# RT1064_Interaction.net
KiCad netlist of a schematic drawn in Altium Designer
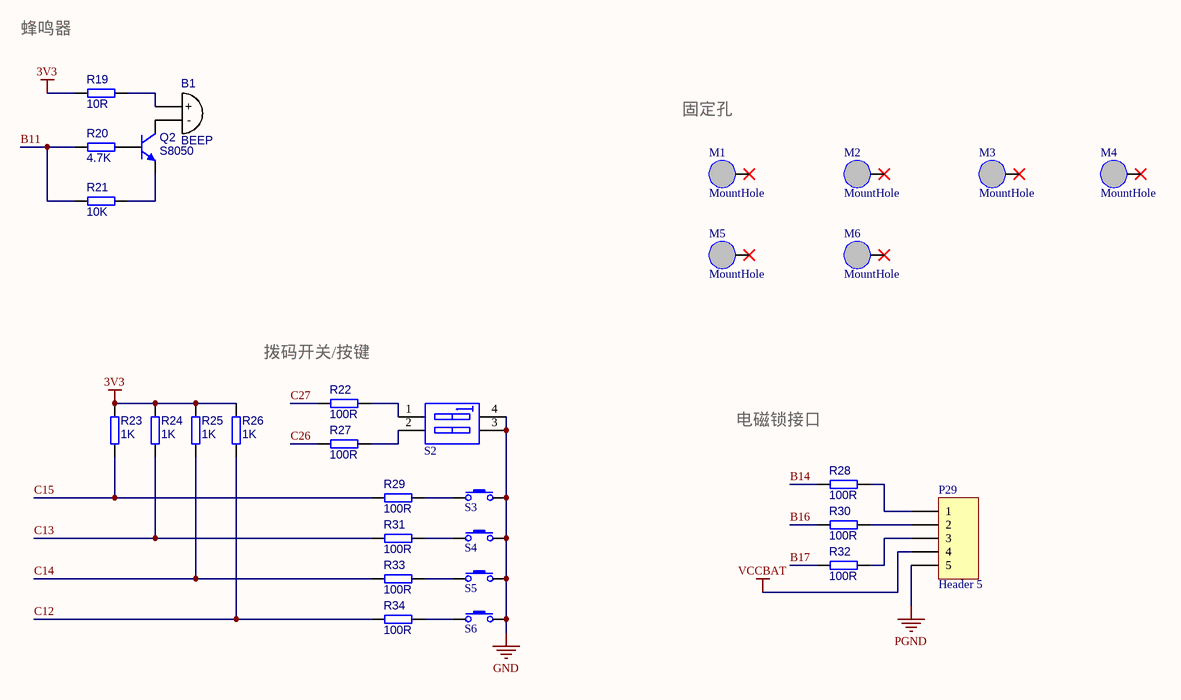
[diagram p0: RT1064_Interaction.SchDoc]

(export (version "E")
  (design (tool "Eeschema 10.0.6"))
  (components
    (comp (ref "B1")
      (value "BEEP")
      (footprint "BEEP 9x5.5mm")
      (description "蜂鸣器")
      (libsource (lib "RT1064_V1主板器件封装集成库") (part "BEEP"))
    )
    (comp (ref "M1")
      (value "MountHole")
      (footprint "M3x12+6_N")
      (description "固定孔")
      (libsource (lib "RT1064_V1主板器件封装集成库") (part "MountHole"))
    )
    (comp (ref "M2")
      (value "MountHole")
      (footprint "M3x12+6_N")
      (description "固定孔")
      (libsource (lib "RT1064_V1主板器件封装集成库") (part "MountHole"))
    )
    (comp (ref "M3")
      (value "MountHole")
      (footprint "M3x12+6_N")
      (description "固定孔")
      (libsource (lib "RT1064_V1主板器件封装集成库") (part "MountHole"))
    )
    (comp (ref "M4")
      (value "MountHole")
      (footprint "M3x12+6_N")
      (description "固定孔")
      (libsource (lib "RT1064_V1主板器件封装集成库") (part "MountHole"))
    )
    (comp (ref "M5")
      (value "MountHole")
      (footprint "M3-MountHole")
      (description "固定孔")
      (libsource (lib "RT1064_V1主板器件封装集成库") (part "MountHole"))
    )
    (comp (ref "M6")
      (value "MountHole")
      (footprint "M3-MountHole")
      (description "固定孔")
      (libsource (lib "RT1064_V1主板器件封装集成库") (part "MountHole"))
    )
    (comp (ref "P29")
      (value "Header 5")
      (footprint "HDR1X5")
      (description "Header, 5-Pin")
      (fields (field (name "PUBLISHER") "Altium Limited"))
      (libsource (lib "Miscellaneous Connectors") (part "Header 5"))
    )
    (comp (ref "Q2")
      (value "S8050")
      (footprint "SOT-23")
      (description "Discrete NPN Bipolar Transistor")
      (fields (field (name "PARTNUMBER") "S8050") (field (name "PUBLISHER") "Altium Limited"))
      (libsource (lib "RT1064_V1主板器件封装集成库") (part "NPN S8050"))
    )
    (comp (ref "R19")
      (value "10R")
      (footprint "RESC1608[0603]S-L")
      (description "贴片电阻")
      (fields (field (name "POWER") "1/8W") (field (name "TOLERANCE") "±1%"))
      (libsource (lib "RT1064_V1主板器件封装集成库") (part "Res-Chip"))
    )
    (comp (ref "R20")
      (value "4.7K")
      (footprint "RESC1608[0603]S-L")
      (description "贴片电阻")
      (fields (field (name "POWER") "1/8W") (field (name "TOLERANCE") "±1%"))
      (libsource (lib "RT1064_V1主板器件封装集成库") (part "Res-Chip"))
    )
    (comp (ref "R21")
      (value "10K")
      (footprint "RESC1608[0603]S-L")
      (description "贴片电阻")
      (fields (field (name "POWER") "1/8W") (field (name "TOLERANCE") "±1%"))
      (libsource (lib "RT1064_V1主板器件封装集成库") (part "Res-Chip"))
    )
    (comp (ref "R22")
      (value "100R")
      (footprint "RESC1608[0603]S-L")
      (description "贴片电阻")
      (fields (field (name "POWER") "1/8W") (field (name "TOLERANCE") "±1%"))
      (libsource (lib "RT1064_V1主板器件封装集成库") (part "Res-Chip"))
    )
    (comp (ref "R23")
      (value "1K")
      (footprint "RESC1608[0603]S-L")
      (description "贴片电阻")
      (fields (field (name "POWER") "1/8W") (field (name "TOLERANCE") "±1%"))
      (libsource (lib "RT1064_V1主板器件封装集成库") (part "Res-Chip"))
    )
    (comp (ref "R24")
      (value "1K")
      (footprint "RESC1608[0603]S-L")
      (description "贴片电阻")
      (fields (field (name "POWER") "1/8W") (field (name "TOLERANCE") "±1%"))
      (libsource (lib "RT1064_V1主板器件封装集成库") (part "Res-Chip"))
    )
    (comp (ref "R25")
      (value "1K")
      (footprint "RESC1608[0603]S-L")
      (description "贴片电阻")
      (fields (field (name "POWER") "1/8W") (field (name "TOLERANCE") "±1%"))
      (libsource (lib "RT1064_V1主板器件封装集成库") (part "Res-Chip"))
    )
    (comp (ref "R26")
      (value "1K")
      (footprint "RESC1608[0603]S-L")
      (description "贴片电阻")
      (fields (field (name "POWER") "1/8W") (field (name "TOLERANCE") "±1%"))
      (libsource (lib "RT1064_V1主板器件封装集成库") (part "Res-Chip"))
    )
    (comp (ref "R27")
      (value "100R")
      (footprint "RESC1608[0603]S-L")
      (description "贴片电阻")
      (fields (field (name "POWER") "1/8W") (field (name "TOLERANCE") "±1%"))
      (libsource (lib "RT1064_V1主板器件封装集成库") (part "Res-Chip"))
    )
    (comp (ref "R28")
      (value "100R")
      (footprint "RESC1608[0603]S-L")
      (description "贴片电阻")
      (fields (field (name "POWER") "1/8W") (field (name "TOLERANCE") "±1%"))
      (libsource (lib "RT1064_V1主板器件封装集成库") (part "Res-Chip"))
    )
    (comp (ref "R29")
      (value "100R")
      (footprint "RESC1608[0603]S-L")
      (description "贴片电阻")
      (fields (field (name "POWER") "1/8W") (field (name "TOLERANCE") "±1%"))
      (libsource (lib "RT1064_V1主板器件封装集成库") (part "Res-Chip"))
    )
    (comp (ref "R30")
      (value "100R")
      (footprint "RESC1608[0603]S-L")
      (description "贴片电阻")
      (fields (field (name "POWER") "1/8W") (field (name "TOLERANCE") "±1%"))
      (libsource (lib "RT1064_V1主板器件封装集成库") (part "Res-Chip"))
    )
    (comp (ref "R31")
      (value "100R")
      (footprint "RESC1608[0603]S-L")
      (description "贴片电阻")
      (fields (field (name "POWER") "1/8W") (field (name "TOLERANCE") "±1%"))
      (libsource (lib "RT1064_V1主板器件封装集成库") (part "Res-Chip"))
    )
    (comp (ref "R32")
      (value "100R")
      (footprint "RESC1608[0603]S-L")
      (description "贴片电阻")
      (fields (field (name "POWER") "1/8W") (field (name "TOLERANCE") "±1%"))
      (libsource (lib "RT1064_V1主板器件封装集成库") (part "Res-Chip"))
    )
    (comp (ref "R33")
      (value "100R")
      (footprint "RESC1608[0603]S-L")
      (description "贴片电阻")
      (fields (field (name "POWER") "1/8W") (field (name "TOLERANCE") "±1%"))
      (libsource (lib "RT1064_V1主板器件封装集成库") (part "Res-Chip"))
    )
    (comp (ref "R34")
      (value "100R")
      (footprint "RESC1608[0603]S-L")
      (description "贴片电阻")
      (fields (field (name "POWER") "1/8W") (field (name "TOLERANCE") "±1%"))
      (libsource (lib "RT1064_V1主板器件封装集成库") (part "Res-Chip"))
    )
    (comp (ref "S2")
      (value "SW DIP-2")
      (footprint "Code SW-2-DIP-2.54")
      (description "2位拨码开关")
      (fields (field (name "PUBLISHER") "Altium Limited"))
      (libsource (lib "RT1064_V1主板器件封装集成库") (part "Code SW-2"))
    )
    (comp (ref "S3")
      (value "Button")
      (footprint "PTS810-3*4-CurvePin")
      (description "按键")
      (fields (field (name "PUBLISHER") "Altium Limited"))
      (libsource (lib "RT1064_V1主板器件封装集成库") (part "KEY"))
    )
    (comp (ref "S4")
      (value "Button")
      (footprint "PTS810-3*4-CurvePin")
      (description "按键")
      (fields (field (name "PUBLISHER") "Altium Limited"))
      (libsource (lib "RT1064_V1主板器件封装集成库") (part "KEY"))
    )
    (comp (ref "S5")
      (value "Button")
      (footprint "PTS810-3*4-CurvePin")
      (description "按键")
      (fields (field (name "PUBLISHER") "Altium Limited"))
      (libsource (lib "RT1064_V1主板器件封装集成库") (part "KEY"))
    )
    (comp (ref "S6")
      (value "Button")
      (footprint "PTS810-3*4-CurvePin")
      (description "按键")
      (fields (field (name "PUBLISHER") "Altium Limited"))
      (libsource (lib "RT1064_V1主板器件封装集成库") (part "KEY"))
    )
  )
  (nets
    (net (code "1") (name "/B11") (class "Default")
      (node (ref "R20") (pin "2") (pinfunction "2_2") (pintype "passive"))
      (node (ref "R21") (pin "2") (pinfunction "2_2") (pintype "passive"))
    )
    (net (code "2") (name "/B14") (class "Default")
      (node (ref "R28") (pin "2") (pinfunction "2_2") (pintype "passive"))
    )
    (net (code "3") (name "/B16") (class "Default")
      (node (ref "R30") (pin "2") (pinfunction "2_2") (pintype "passive"))
    )
    (net (code "4") (name "/B17") (class "Default")
      (node (ref "R32") (pin "2") (pinfunction "2_2") (pintype "passive"))
    )
    (net (code "5") (name "/C12") (class "Default")
      (node (ref "R26") (pin "2") (pinfunction "2_2") (pintype "passive"))
      (node (ref "R34") (pin "2") (pinfunction "2_2") (pintype "passive"))
    )
    (net (code "6") (name "/C13") (class "Default")
      (node (ref "R24") (pin "2") (pinfunction "2_2") (pintype "passive"))
      (node (ref "R31") (pin "2") (pinfunction "2_2") (pintype "passive"))
    )
    (net (code "7") (name "/C14") (class "Default")
      (node (ref "R25") (pin "2") (pinfunction "2_2") (pintype "passive"))
      (node (ref "R33") (pin "2") (pinfunction "2_2") (pintype "passive"))
    )
    (net (code "8") (name "/C15") (class "Default")
      (node (ref "R23") (pin "2") (pinfunction "2_2") (pintype "passive"))
      (node (ref "R29") (pin "2") (pinfunction "2_2") (pintype "passive"))
    )
    (net (code "9") (name "/C26") (class "Default")
      (node (ref "R27") (pin "2") (pinfunction "2_2") (pintype "passive"))
    )
    (net (code "10") (name "/C27") (class "Default")
      (node (ref "R22") (pin "2") (pinfunction "2_2") (pintype "passive"))
    )
    (net (code "11") (name "3V3") (class "Default")
      (node (ref "R19") (pin "2") (pinfunction "2_2") (pintype "passive"))
      (node (ref "R23") (pin "1") (pinfunction "1_1") (pintype "passive"))
      (node (ref "R24") (pin "1") (pinfunction "1_1") (pintype "passive"))
      (node (ref "R25") (pin "1") (pinfunction "1_1") (pintype "passive"))
      (node (ref "R26") (pin "1") (pinfunction "1_1") (pintype "passive"))
    )
    (net (code "12") (name "GND") (class "Default")
      (node (ref "S2") (pin "3") (pinfunction "B2_3") (pintype "passive"))
      (node (ref "S2") (pin "4") (pinfunction "B1_4") (pintype "passive"))
      (node (ref "S3") (pin "1") (pinfunction "1_1") (pintype "passive"))
      (node (ref "S4") (pin "1") (pinfunction "1_1") (pintype "passive"))
      (node (ref "S5") (pin "1") (pinfunction "1_1") (pintype "passive"))
      (node (ref "S6") (pin "1") (pinfunction "1_1") (pintype "passive"))
    )
    (net (code "13") (name "Net-(B1-+)") (class "Default")
      (node (ref "B1") (pin "1") (pinfunction "+_1") (pintype "passive"))
      (node (ref "R19") (pin "1") (pinfunction "1_1") (pintype "passive"))
    )
    (net (code "14") (name "Net-(B1--)") (class "Default")
      (node (ref "B1") (pin "2") (pinfunction "-_2") (pintype "passive"))
      (node (ref "Q2") (pin "3") (pinfunction "C_3") (pintype "passive"))
    )
    (net (code "15") (name "Net-(P29-Pad1)") (class "Default")
      (node (ref "P29") (pin "1") (pinfunction "1_1") (pintype "passive"))
      (node (ref "R28") (pin "1") (pinfunction "1_1") (pintype "passive"))
    )
    (net (code "16") (name "Net-(P29-Pad2)") (class "Default")
      (node (ref "P29") (pin "2") (pinfunction "2_2") (pintype "passive"))
      (node (ref "R30") (pin "1") (pinfunction "1_1") (pintype "passive"))
    )
    (net (code "17") (name "Net-(P29-Pad3)") (class "Default")
      (node (ref "P29") (pin "3") (pinfunction "3_3") (pintype "passive"))
      (node (ref "R32") (pin "1") (pinfunction "1_1") (pintype "passive"))
    )
    (net (code "18") (name "Net-(Q2-B)") (class "Default")
      (node (ref "Q2") (pin "1") (pinfunction "B_1") (pintype "passive"))
      (node (ref "R20") (pin "1") (pinfunction "1_1") (pintype "passive"))
    )
    (net (code "19") (name "Net-(Q2-E)") (class "Default")
      (node (ref "Q2") (pin "2") (pinfunction "E_2") (pintype "passive"))
      (node (ref "R21") (pin "1") (pinfunction "1_1") (pintype "passive"))
    )
    (net (code "20") (name "Net-(R29-Pad1)") (class "Default")
      (node (ref "R29") (pin "1") (pinfunction "1_1") (pintype "passive"))
      (node (ref "S3") (pin "2") (pinfunction "2_2") (pintype "passive"))
    )
    (net (code "21") (name "Net-(R31-Pad1)") (class "Default")
      (node (ref "R31") (pin "1") (pinfunction "1_1") (pintype "passive"))
      (node (ref "S4") (pin "2") (pinfunction "2_2") (pintype "passive"))
    )
    (net (code "22") (name "Net-(R33-Pad1)") (class "Default")
      (node (ref "R33") (pin "1") (pinfunction "1_1") (pintype "passive"))
      (node (ref "S5") (pin "2") (pinfunction "2_2") (pintype "passive"))
    )
    (net (code "23") (name "Net-(R34-Pad1)") (class "Default")
      (node (ref "R34") (pin "1") (pinfunction "1_1") (pintype "passive"))
      (node (ref "S6") (pin "2") (pinfunction "2_2") (pintype "passive"))
    )
    (net (code "24") (name "Net-(S2-A1)") (class "Default")
      (node (ref "R22") (pin "1") (pinfunction "1_1") (pintype "passive"))
      (node (ref "S2") (pin "1") (pinfunction "A1_1") (pintype "passive"))
    )
    (net (code "25") (name "Net-(S2-A2)") (class "Default")
      (node (ref "R27") (pin "1") (pinfunction "1_1") (pintype "passive"))
      (node (ref "S2") (pin "2") (pinfunction "A2_2") (pintype "passive"))
    )
    (net (code "26") (name "PGND") (class "Default")
      (node (ref "P29") (pin "5") (pinfunction "5_5") (pintype "passive"))
    )
    (net (code "27") (name "VCCBAT") (class "Default")
      (node (ref "P29") (pin "4") (pinfunction "4_4") (pintype "passive"))
    )
    (net (code "28") (name "unconnected-(M1-Pad1)") (class "Default")
      (node (ref "M1") (pin "1") (pinfunction "1_1") (pintype "passive+no_connect"))
    )
    (net (code "29") (name "unconnected-(M2-Pad1)") (class "Default")
      (node (ref "M2") (pin "1") (pinfunction "1_1") (pintype "passive+no_connect"))
    )
    (net (code "30") (name "unconnected-(M3-Pad1)") (class "Default")
      (node (ref "M3") (pin "1") (pinfunction "1_1") (pintype "passive+no_connect"))
    )
    (net (code "31") (name "unconnected-(M4-Pad1)") (class "Default")
      (node (ref "M4") (pin "1") (pinfunction "1_1") (pintype "passive+no_connect"))
    )
    (net (code "32") (name "unconnected-(M5-Pad1)") (class "Default")
      (node (ref "M5") (pin "1") (pinfunction "1_1") (pintype "passive+no_connect"))
    )
    (net (code "33") (name "unconnected-(M6-Pad1)") (class "Default")
      (node (ref "M6") (pin "1") (pinfunction "1_1") (pintype "passive+no_connect"))
    )
  )
)
